# 5Vto3V3_Power_Connector.net
KiCad netlist of a schematic drawn in Altium Designer
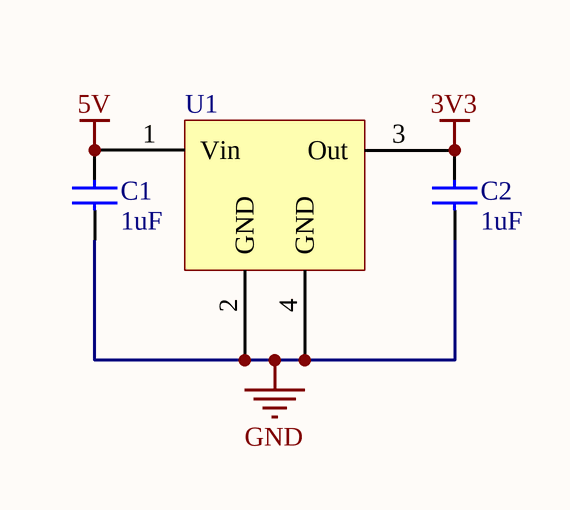
[diagram p0: 5Vto3V3_Power_Connector.SchDoc]

(export (version "E")
  (design (tool "Eeschema 10.0.6"))
  (components
    (comp (ref "C1")
      (value "1uF")
      (footprint "CAPC0603")
      (fields (field (name "Comment") "Cap"))
      (libsource (lib "SubjuGator8") (part "Cap"))
    )
    (comp (ref "C2")
      (value "1uF")
      (footprint "CAPC0603")
      (fields (field (name "Comment") "Cap"))
      (libsource (lib "SubjuGator8") (part "Cap"))
    )
    (comp (ref "U1")
      (value "3.3V LDO Reg")
      (footprint "SOT23-4n")
      (description "IC REG LDO 3.3V 1A SOT223")
      (libsource (lib "SubjuGator8") (part "LM3940IMPX-3.3"))
    )
  )
  (nets
    (net (code "1") (name "3V3") (class "Default")
      (node (ref "C2") (pin "1") (pinfunction "A_1") (pintype "passive"))
      (node (ref "U1") (pin "3") (pinfunction "Out_3") (pintype "passive"))
    )
    (net (code "2") (name "5V") (class "Default")
      (node (ref "C1") (pin "1") (pinfunction "A_1") (pintype "passive"))
      (node (ref "U1") (pin "1") (pinfunction "Vin_1") (pintype "passive"))
    )
    (net (code "3") (name "GND") (class "Default")
      (node (ref "C1") (pin "2") (pinfunction "B_2") (pintype "passive"))
      (node (ref "C2") (pin "2") (pinfunction "B_2") (pintype "passive"))
      (node (ref "U1") (pin "2") (pinfunction "GND_2") (pintype "passive"))
      (node (ref "U1") (pin "4") (pinfunction "GND_4") (pintype "passive"))
    )
  )
)
